# MODUL_RAIL_IN_V100.net
KiCad netlist of a schematic drawn in EAGLE
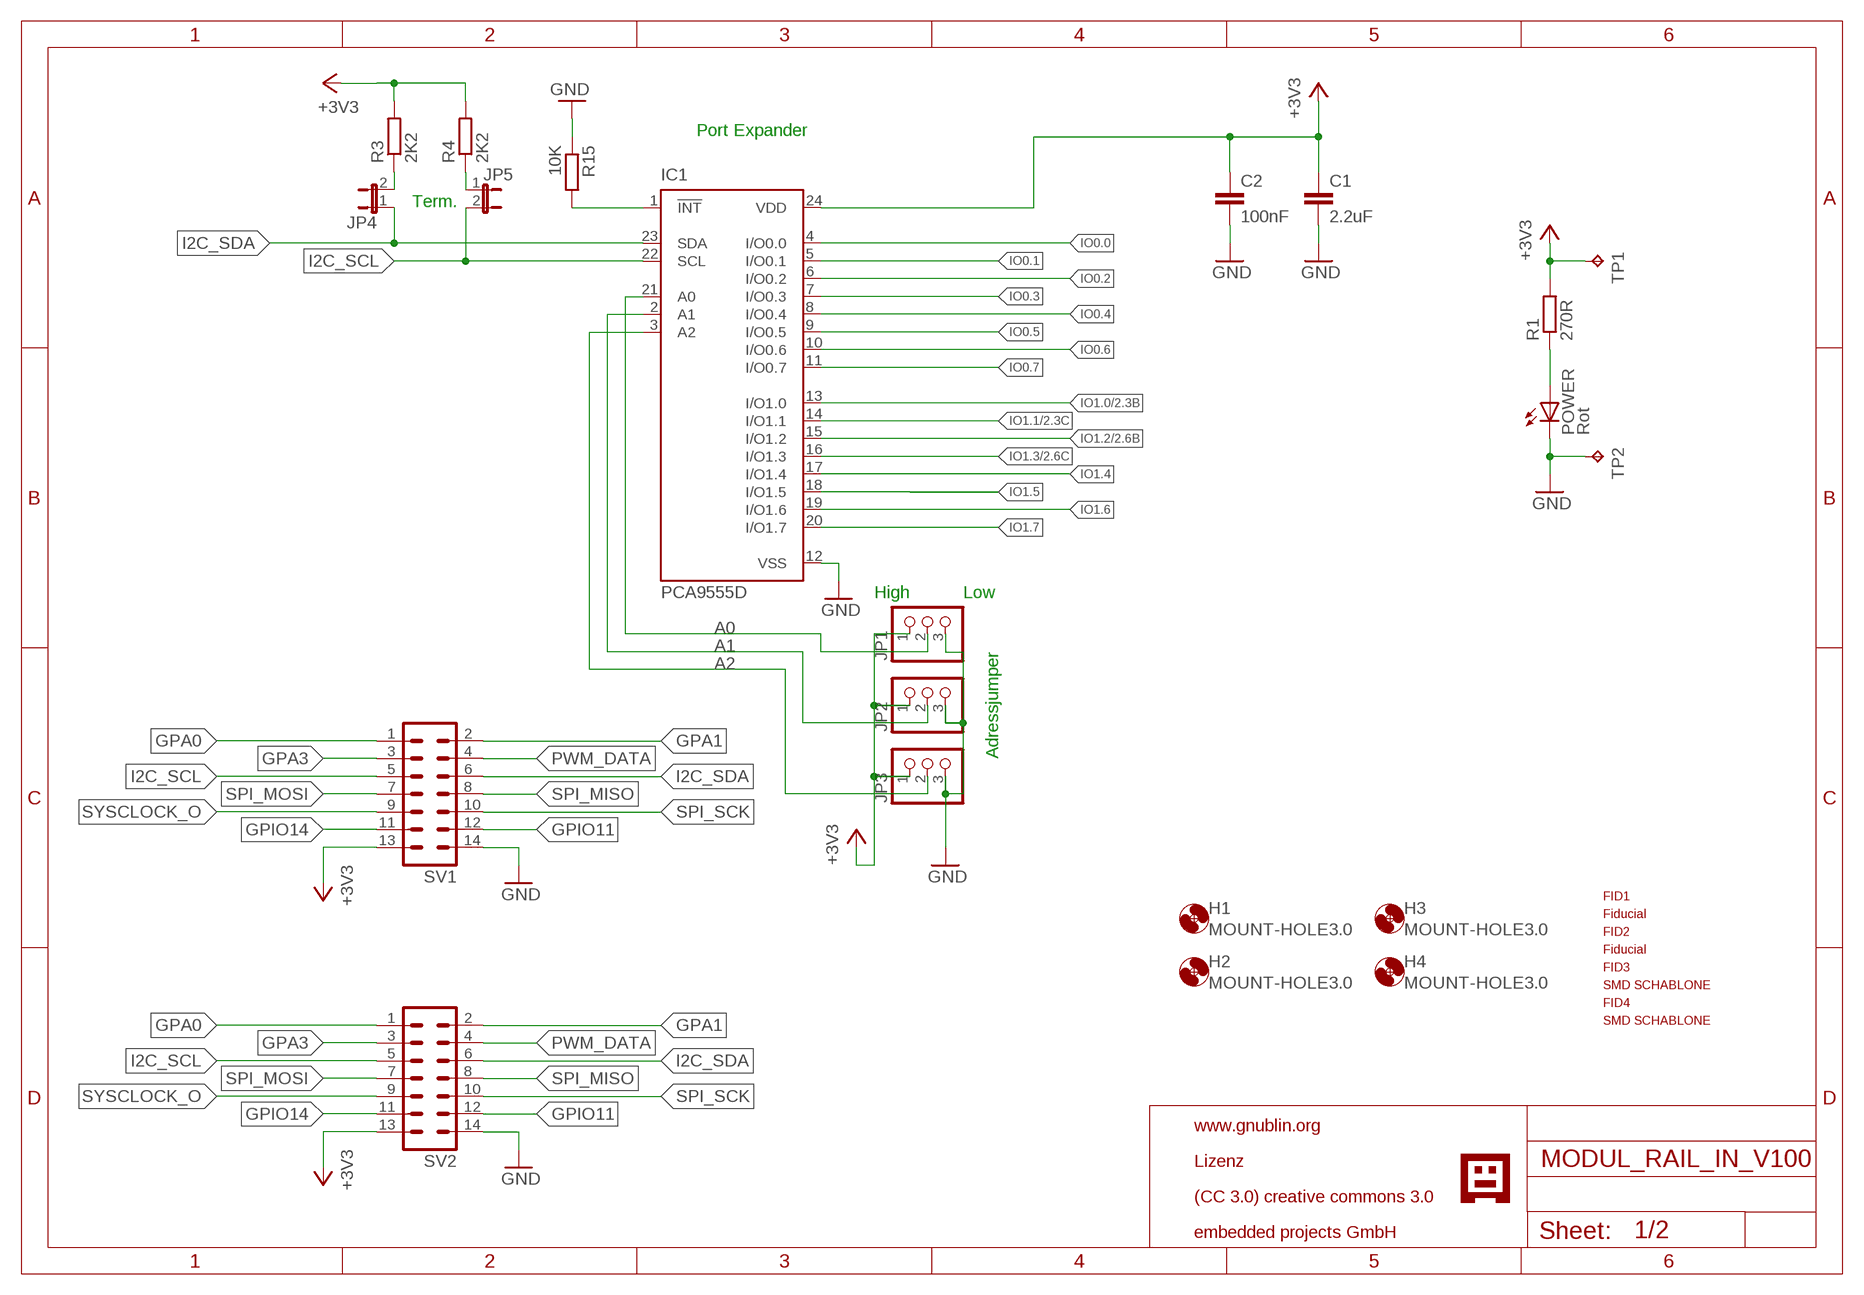
[diagram p0: schematic, sheet 1]
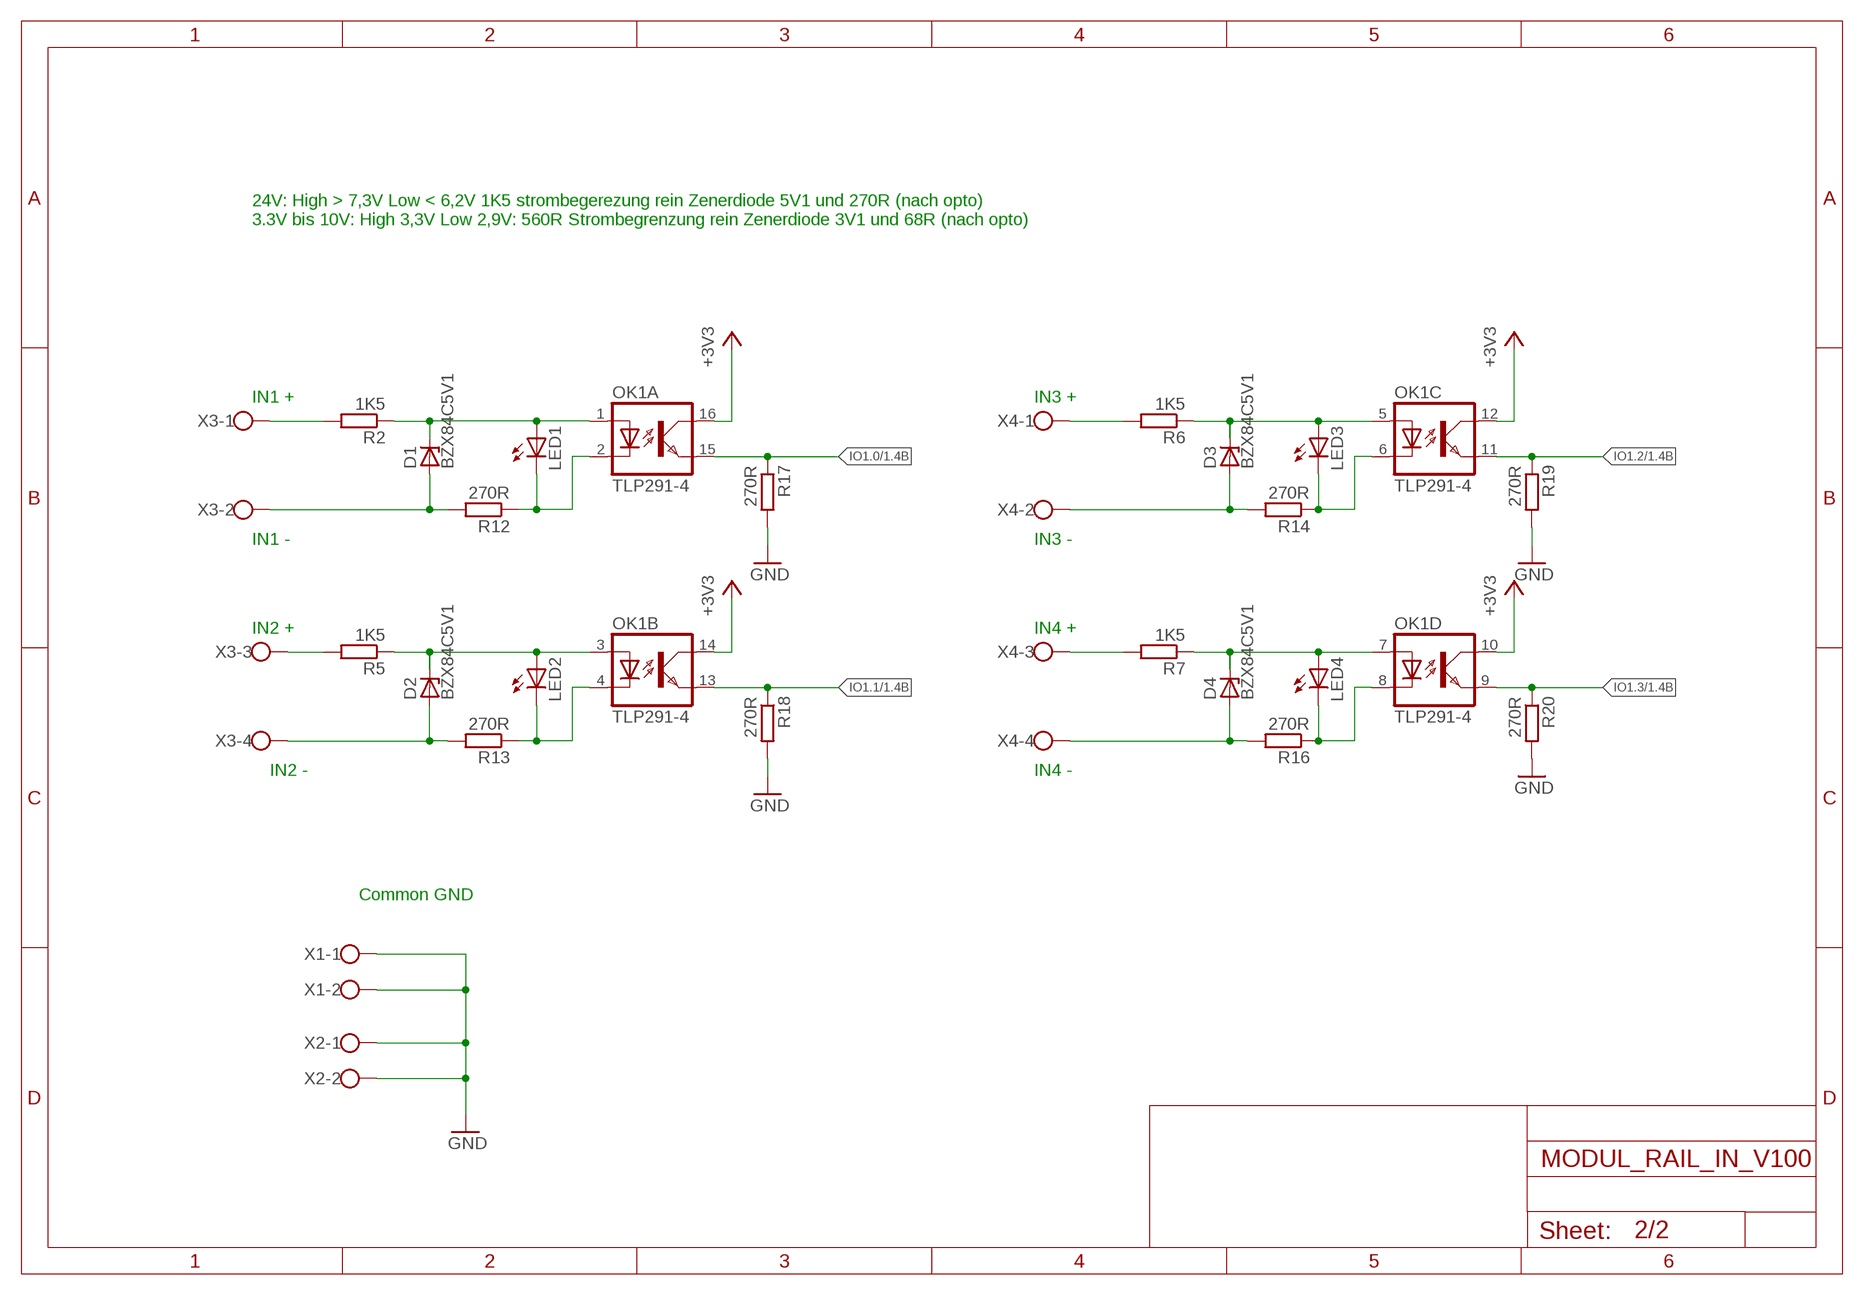
[diagram p1: schematic, sheet 2]

(export (version "E")
  (design (tool "Eeschema 10.0.6"))
  (components
    (comp (ref "C1")
      (value "2.2uF")
      (footprint "eagle-import:C0805")
      (libsource (lib "eagle-import") (part "C-EUC0805"))
    )
    (comp (ref "C2")
      (value "100nF")
      (footprint "eagle-import:C0805")
      (libsource (lib "eagle-import") (part "C-EUC0805"))
    )
    (comp (ref "FID1")
      (value "PASSERMARKEN_FIDUCIAL")
      (footprint "eagle-import:PASSERMARKEN_FIDUCIAL")
      (libsource (lib "eagle-import") (part "PASSERMARKEN_FIDUCIAL"))
    )
    (comp (ref "FID2")
      (value "PASSERMARKEN_FIDUCIAL")
      (footprint "eagle-import:PASSERMARKEN_FIDUCIAL")
      (libsource (lib "eagle-import") (part "PASSERMARKEN_FIDUCIAL"))
    )
    (comp (ref "FID3")
      (value "PASSERMARKEN_FIDUCIAL")
      (footprint "eagle-import:PASSERMARKEN_FIDUCIAL")
      (libsource (lib "eagle-import") (part "SMDSCHABLONE_PASSERMARKEN_FIDUCIAL"))
    )
    (comp (ref "FID4")
      (value "PASSERMARKEN_FIDUCIAL")
      (footprint "eagle-import:PASSERMARKEN_FIDUCIAL")
      (libsource (lib "eagle-import") (part "SMDSCHABLONE_PASSERMARKEN_FIDUCIAL"))
    )
    (comp (ref "H1")
      (value "MOUNT-HOLE3.0")
      (footprint "eagle-import:3,0")
      (libsource (lib "eagle-import") (part "MOUNT-HOLE3.0"))
    )
    (comp (ref "H2")
      (value "MOUNT-HOLE3.0")
      (footprint "eagle-import:3,0")
      (libsource (lib "eagle-import") (part "MOUNT-HOLE3.0"))
    )
    (comp (ref "H3")
      (value "MOUNT-HOLE3.0")
      (footprint "eagle-import:3,0")
      (libsource (lib "eagle-import") (part "MOUNT-HOLE3.0"))
    )
    (comp (ref "H4")
      (value "MOUNT-HOLE3.0")
      (footprint "eagle-import:3,0")
      (libsource (lib "eagle-import") (part "MOUNT-HOLE3.0"))
    )
    (comp (ref "IC1")
      (value "PCA9555D")
      (footprint "eagle-import:SO24")
      (fields (field (name "MPN") "PCA9555DW") (field (name "OC_FARNELL") "8906076"))
      (libsource (lib "eagle-import") (part "PCA9555D"))
    )
    (comp (ref "JP1")
      (value "PINHD-1X3")
      (footprint "eagle-import:1X03")
      (libsource (lib "eagle-import") (part "PINHD-1X3"))
    )
    (comp (ref "JP2")
      (value "PINHD-1X3")
      (footprint "eagle-import:1X03")
      (libsource (lib "eagle-import") (part "PINHD-1X3"))
    )
    (comp (ref "JP3")
      (value "PINHD-1X3")
      (footprint "eagle-import:1X03")
      (libsource (lib "eagle-import") (part "PINHD-1X3"))
    )
    (comp (ref "JP4")
      (value "JP1E")
      (footprint "eagle-import:JP1")
      (libsource (lib "eagle-import") (part "JP1E"))
    )
    (comp (ref "JP5")
      (value "JP1E")
      (footprint "eagle-import:JP1")
      (libsource (lib "eagle-import") (part "JP1E"))
    )
    (comp (ref "POWER")
      (value "Rot")
      (footprint "eagle-import:CHIP-LED0805")
      (libsource (lib "eagle-import") (part "LEDCHIP-LED0805"))
    )
    (comp (ref "R1")
      (value "270R")
      (footprint "eagle-import:R0805")
      (libsource (lib "eagle-import") (part "R-EU_R0805"))
    )
    (comp (ref "R3")
      (value "2K2")
      (footprint "eagle-import:R0805")
      (libsource (lib "eagle-import") (part "R-EU_R0805"))
    )
    (comp (ref "R4")
      (value "2K2")
      (footprint "eagle-import:R0805")
      (libsource (lib "eagle-import") (part "R-EU_R0805"))
    )
    (comp (ref "R15")
      (value "10K")
      (footprint "eagle-import:R0805")
      (libsource (lib "eagle-import") (part "R-EU_R0805"))
    )
    (comp (ref "SV1")
      (value "ML14")
      (footprint "eagle-import:ML14")
      (libsource (lib "eagle-import") (part "ML14"))
    )
    (comp (ref "SV2")
      (value "ML14")
      (footprint "eagle-import:ML14")
      (libsource (lib "eagle-import") (part "ML14"))
    )
    (comp (ref "TP1")
      (value "TPB1,27")
      (footprint "eagle-import:B1,27")
      (libsource (lib "eagle-import") (part "TPB1,27"))
    )
    (comp (ref "TP2")
      (value "TPB1,27")
      (footprint "eagle-import:B1,27")
      (libsource (lib "eagle-import") (part "TPB1,27"))
    )
    (comp (ref "U$2")
      (value "GNUBLINLOGOSIEB")
      (footprint "eagle-import:GNUSIEBDRUCK")
      (libsource (lib "eagle-import") (part "GNUBLINLOGOSIEB"))
    )
    (comp (ref "D1")
      (value "BZX84C5V1")
      (footprint "eagle-import:TO236")
      (libsource (lib "eagle-import") (part "BZX84CSMD"))
    )
    (comp (ref "D2")
      (value "BZX84C5V1")
      (footprint "eagle-import:TO236")
      (libsource (lib "eagle-import") (part "BZX84CSMD"))
    )
    (comp (ref "D3")
      (value "BZX84C5V1")
      (footprint "eagle-import:TO236")
      (libsource (lib "eagle-import") (part "BZX84CSMD"))
    )
    (comp (ref "D4")
      (value "BZX84C5V1")
      (footprint "eagle-import:TO236")
      (libsource (lib "eagle-import") (part "BZX84CSMD"))
    )
    (comp (ref "LED1")
      (value "LEDCHIPLED_0805")
      (footprint "eagle-import:CHIPLED_0805")
      (libsource (lib "eagle-import") (part "LEDCHIPLED_0805"))
    )
    (comp (ref "LED2")
      (value "LEDCHIPLED_0805")
      (footprint "eagle-import:CHIPLED_0805")
      (libsource (lib "eagle-import") (part "LEDCHIPLED_0805"))
    )
    (comp (ref "LED3")
      (value "LEDCHIPLED_0805")
      (footprint "eagle-import:CHIPLED_0805")
      (libsource (lib "eagle-import") (part "LEDCHIPLED_0805"))
    )
    (comp (ref "LED4")
      (value "LEDCHIPLED_0805")
      (footprint "eagle-import:CHIPLED_0805")
      (libsource (lib "eagle-import") (part "LEDCHIPLED_0805"))
    )
    (comp (ref "OK1")
      (value "TLP291-4")
      (footprint "eagle-import:MINI-FLAT-16")
      (libsource (lib "eagle-import") (part "TLP283-4"))
    )
    (comp (ref "R2")
      (value "1K5")
      (footprint "eagle-import:R0805")
      (libsource (lib "eagle-import") (part "R-EU_R0805"))
    )
    (comp (ref "R5")
      (value "1K5")
      (footprint "eagle-import:R0805")
      (libsource (lib "eagle-import") (part "R-EU_R0805"))
    )
    (comp (ref "R6")
      (value "1K5")
      (footprint "eagle-import:R0805")
      (libsource (lib "eagle-import") (part "R-EU_R0805"))
    )
    (comp (ref "R7")
      (value "1K5")
      (footprint "eagle-import:R0805")
      (libsource (lib "eagle-import") (part "R-EU_R0805"))
    )
    (comp (ref "R12")
      (value "270R")
      (footprint "eagle-import:R0805")
      (libsource (lib "eagle-import") (part "R-EU_R0805"))
    )
    (comp (ref "R13")
      (value "270R")
      (footprint "eagle-import:R0805")
      (libsource (lib "eagle-import") (part "R-EU_R0805"))
    )
    (comp (ref "R14")
      (value "270R")
      (footprint "eagle-import:R0805")
      (libsource (lib "eagle-import") (part "R-EU_R0805"))
    )
    (comp (ref "R16")
      (value "270R")
      (footprint "eagle-import:R0805")
      (libsource (lib "eagle-import") (part "R-EU_R0805"))
    )
    (comp (ref "R17")
      (value "270R")
      (footprint "eagle-import:R0805")
      (libsource (lib "eagle-import") (part "R-EU_R0805"))
    )
    (comp (ref "R18")
      (value "270R")
      (footprint "eagle-import:R0805")
      (libsource (lib "eagle-import") (part "R-EU_R0805"))
    )
    (comp (ref "R19")
      (value "270R")
      (footprint "eagle-import:R0805")
      (libsource (lib "eagle-import") (part "R-EU_R0805"))
    )
    (comp (ref "R20")
      (value "270R")
      (footprint "eagle-import:R0805")
      (libsource (lib "eagle-import") (part "R-EU_R0805"))
    )
    (comp (ref "X1")
      (value "W237-02P")
      (footprint "eagle-import:W237-132")
      (libsource (lib "eagle-import") (part "W237-02P"))
    )
    (comp (ref "X2")
      (value "W237-02P")
      (footprint "eagle-import:W237-132")
      (libsource (lib "eagle-import") (part "W237-02P"))
    )
    (comp (ref "X3")
      (value "W237-04P")
      (footprint "eagle-import:W237-4P")
      (libsource (lib "eagle-import") (part "W237-04P"))
    )
    (comp (ref "X4")
      (value "W237-04P")
      (footprint "eagle-import:W237-4P")
      (libsource (lib "eagle-import") (part "W237-04P"))
    )
  )
  (nets
    (net (code "1") (name "+3V3") (class "Default")
      (node (ref "C1") (pin "1") (pinfunction "1_1") (pintype "passive"))
      (node (ref "C2") (pin "1") (pinfunction "1_1") (pintype "passive"))
      (node (ref "IC1") (pin "24") (pinfunction "VDD_24") (pintype "power_in"))
      (node (ref "JP1") (pin "1") (pinfunction "1_1") (pintype "passive"))
      (node (ref "JP2") (pin "1") (pinfunction "1_1") (pintype "passive"))
      (node (ref "JP3") (pin "1") (pinfunction "1_1") (pintype "passive"))
      (node (ref "OK1") (pin "10") (pinfunction "COL_10") (pintype "passive"))
      (node (ref "OK1") (pin "12") (pinfunction "COL_12") (pintype "passive"))
      (node (ref "OK1") (pin "14") (pinfunction "COL_14") (pintype "passive"))
      (node (ref "OK1") (pin "16") (pinfunction "COL_16") (pintype "passive"))
      (node (ref "R1") (pin "2") (pinfunction "2_2") (pintype "passive"))
      (node (ref "R3") (pin "2") (pinfunction "2_2") (pintype "passive"))
      (node (ref "R4") (pin "2") (pinfunction "2_2") (pintype "passive"))
      (node (ref "SV1") (pin "13") (pinfunction "13_13") (pintype "passive"))
      (node (ref "SV2") (pin "13") (pinfunction "13_13") (pintype "passive"))
      (node (ref "TP1") (pin "TP") (pinfunction "TP_TP") (pintype "input"))
    )
    (net (code "2") (name "A0") (class "Default")
      (node (ref "IC1") (pin "21") (pinfunction "A0_21") (pintype "input"))
      (node (ref "JP1") (pin "2") (pinfunction "2_2") (pintype "passive"))
    )
    (net (code "3") (name "A1") (class "Default")
      (node (ref "IC1") (pin "2") (pinfunction "A1_2") (pintype "input"))
      (node (ref "JP2") (pin "2") (pinfunction "2_2") (pintype "passive"))
    )
    (net (code "4") (name "A2") (class "Default")
      (node (ref "IC1") (pin "3") (pinfunction "A2_3") (pintype "input"))
      (node (ref "JP3") (pin "2") (pinfunction "2_2") (pintype "passive"))
    )
    (net (code "5") (name "GND") (class "Default")
      (node (ref "C1") (pin "2") (pinfunction "2_2") (pintype "passive"))
      (node (ref "C2") (pin "2") (pinfunction "2_2") (pintype "passive"))
      (node (ref "IC1") (pin "12") (pinfunction "VSS_12") (pintype "power_in"))
      (node (ref "JP1") (pin "3") (pinfunction "3_3") (pintype "passive"))
      (node (ref "JP2") (pin "3") (pinfunction "3_3") (pintype "passive"))
      (node (ref "JP3") (pin "3") (pinfunction "3_3") (pintype "passive"))
      (node (ref "POWER") (pin "C") (pinfunction "C_C") (pintype "passive"))
      (node (ref "R15") (pin "1") (pinfunction "1_1") (pintype "passive"))
      (node (ref "R17") (pin "2") (pinfunction "2_2") (pintype "passive"))
      (node (ref "R18") (pin "2") (pinfunction "2_2") (pintype "passive"))
      (node (ref "R19") (pin "2") (pinfunction "2_2") (pintype "passive"))
      (node (ref "R20") (pin "2") (pinfunction "2_2") (pintype "passive"))
      (node (ref "SV1") (pin "14") (pinfunction "14_14") (pintype "passive"))
      (node (ref "SV2") (pin "14") (pinfunction "14_14") (pintype "passive"))
      (node (ref "TP2") (pin "TP") (pinfunction "TP_TP") (pintype "input"))
      (node (ref "X1") (pin "1") (pinfunction "KL_1") (pintype "passive"))
      (node (ref "X1") (pin "2") (pinfunction "KL_2") (pintype "passive"))
      (node (ref "X2") (pin "1") (pinfunction "KL_1") (pintype "passive"))
      (node (ref "X2") (pin "2") (pinfunction "KL_2") (pintype "passive"))
    )
    (net (code "6") (name "GPA0") (class "Default")
      (node (ref "SV1") (pin "1") (pinfunction "1_1") (pintype "passive"))
      (node (ref "SV2") (pin "1") (pinfunction "1_1") (pintype "passive"))
    )
    (net (code "7") (name "GPA1") (class "Default")
      (node (ref "SV1") (pin "2") (pinfunction "2_2") (pintype "passive"))
      (node (ref "SV2") (pin "2") (pinfunction "2_2") (pintype "passive"))
    )
    (net (code "8") (name "GPA3") (class "Default")
      (node (ref "SV1") (pin "3") (pinfunction "3_3") (pintype "passive"))
      (node (ref "SV2") (pin "3") (pinfunction "3_3") (pintype "passive"))
    )
    (net (code "9") (name "GPIO11") (class "Default")
      (node (ref "SV1") (pin "12") (pinfunction "12_12") (pintype "passive"))
      (node (ref "SV2") (pin "12") (pinfunction "12_12") (pintype "passive"))
    )
    (net (code "10") (name "GPIO14") (class "Default")
      (node (ref "SV1") (pin "11") (pinfunction "11_11") (pintype "passive"))
      (node (ref "SV2") (pin "11") (pinfunction "11_11") (pintype "passive"))
    )
    (net (code "11") (name "I2C_SCL") (class "Default")
      (node (ref "IC1") (pin "22") (pinfunction "SCL_22") (pintype "input"))
      (node (ref "JP5") (pin "2") (pinfunction "2_2") (pintype "passive"))
      (node (ref "SV1") (pin "5") (pinfunction "5_5") (pintype "passive"))
      (node (ref "SV2") (pin "5") (pinfunction "5_5") (pintype "passive"))
    )
    (net (code "12") (name "I2C_SDA") (class "Default")
      (node (ref "IC1") (pin "23") (pinfunction "SDA_23") (pintype "bidirectional"))
      (node (ref "JP4") (pin "1") (pinfunction "1_1") (pintype "passive"))
      (node (ref "SV1") (pin "6") (pinfunction "6_6") (pintype "passive"))
      (node (ref "SV2") (pin "6") (pinfunction "6_6") (pintype "passive"))
    )
    (net (code "13") (name "IO0.0") (class "Default")
      (node (ref "IC1") (pin "4") (pinfunction "I/O0.0_4") (pintype "bidirectional"))
    )
    (net (code "14") (name "IO0.1") (class "Default")
      (node (ref "IC1") (pin "5") (pinfunction "I/O0.1_5") (pintype "bidirectional"))
    )
    (net (code "15") (name "IO0.2") (class "Default")
      (node (ref "IC1") (pin "6") (pinfunction "I/O0.2_6") (pintype "bidirectional"))
    )
    (net (code "16") (name "IO0.3") (class "Default")
      (node (ref "IC1") (pin "7") (pinfunction "I/O0.3_7") (pintype "bidirectional"))
    )
    (net (code "17") (name "IO0.4") (class "Default")
      (node (ref "IC1") (pin "8") (pinfunction "I/O0.4_8") (pintype "bidirectional"))
    )
    (net (code "18") (name "IO0.5") (class "Default")
      (node (ref "IC1") (pin "9") (pinfunction "I/O0.5_9") (pintype "bidirectional"))
    )
    (net (code "19") (name "IO0.6") (class "Default")
      (node (ref "IC1") (pin "10") (pinfunction "I/O0.6_10") (pintype "bidirectional"))
    )
    (net (code "20") (name "IO0.7") (class "Default")
      (node (ref "IC1") (pin "11") (pinfunction "I/O0.7_11") (pintype "bidirectional"))
    )
    (net (code "21") (name "IO1.0") (class "Default")
      (node (ref "IC1") (pin "13") (pinfunction "I/O1.0_13") (pintype "bidirectional"))
      (node (ref "OK1") (pin "15") (pinfunction "EMIT_15") (pintype "passive"))
      (node (ref "R17") (pin "1") (pinfunction "1_1") (pintype "passive"))
    )
    (net (code "22") (name "IO1.1") (class "Default")
      (node (ref "IC1") (pin "14") (pinfunction "I/O1.1_14") (pintype "bidirectional"))
      (node (ref "OK1") (pin "13") (pinfunction "EMIT_13") (pintype "passive"))
      (node (ref "R18") (pin "1") (pinfunction "1_1") (pintype "passive"))
    )
    (net (code "23") (name "IO1.2") (class "Default")
      (node (ref "IC1") (pin "15") (pinfunction "I/O1.2_15") (pintype "bidirectional"))
      (node (ref "OK1") (pin "11") (pinfunction "EMIT_11") (pintype "passive"))
      (node (ref "R19") (pin "1") (pinfunction "1_1") (pintype "passive"))
    )
    (net (code "24") (name "IO1.3") (class "Default")
      (node (ref "IC1") (pin "16") (pinfunction "I/O1.3_16") (pintype "bidirectional"))
      (node (ref "OK1") (pin "9") (pinfunction "EMIT_9") (pintype "passive"))
      (node (ref "R20") (pin "1") (pinfunction "1_1") (pintype "passive"))
    )
    (net (code "25") (name "IO1.4") (class "Default")
      (node (ref "IC1") (pin "17") (pinfunction "I/O1.4_17") (pintype "bidirectional"))
    )
    (net (code "26") (name "IO1.5") (class "Default")
      (node (ref "IC1") (pin "18") (pinfunction "I/O1.5_18") (pintype "bidirectional"))
    )
    (net (code "27") (name "IO1.6") (class "Default")
      (node (ref "IC1") (pin "19") (pinfunction "I/O1.6_19") (pintype "bidirectional"))
    )
    (net (code "28") (name "IO1.7") (class "Default")
      (node (ref "IC1") (pin "20") (pinfunction "I/O1.7_20") (pintype "bidirectional"))
    )
    (net (code "29") (name "Net-(IC1-~{INT})") (class "Default")
      (node (ref "IC1") (pin "1") (pinfunction "~{INT}_1") (pintype "output"))
      (node (ref "R15") (pin "2") (pinfunction "2_2") (pintype "passive"))
    )
    (net (code "30") (name "Net-(JP4-Pad2)") (class "Default")
      (node (ref "JP4") (pin "2") (pinfunction "2_2") (pintype "passive"))
      (node (ref "R3") (pin "1") (pinfunction "1_1") (pintype "passive"))
    )
    (net (code "31") (name "Net-(JP5-Pad1)") (class "Default")
      (node (ref "JP5") (pin "1") (pinfunction "1_1") (pintype "passive"))
      (node (ref "R4") (pin "1") (pinfunction "1_1") (pintype "passive"))
    )
    (net (code "32") (name "Net-(OK1A-A)") (class "Default")
      (node (ref "D1") (pin "C") (pinfunction "C_C") (pintype "passive"))
      (node (ref "LED1") (pin "A") (pinfunction "A_A") (pintype "passive"))
      (node (ref "OK1") (pin "1") (pinfunction "A_1") (pintype "passive"))
      (node (ref "R2") (pin "1") (pinfunction "1_1") (pintype "passive"))
    )
    (net (code "33") (name "Net-(OK1A-C)") (class "Default")
      (node (ref "LED1") (pin "C") (pinfunction "C_C") (pintype "passive"))
      (node (ref "OK1") (pin "2") (pinfunction "C_2") (pintype "passive"))
      (node (ref "R12") (pin "1") (pinfunction "1_1") (pintype "passive"))
    )
    (net (code "34") (name "Net-(OK1B-A)") (class "Default")
      (node (ref "D2") (pin "C") (pinfunction "C_C") (pintype "passive"))
      (node (ref "LED2") (pin "A") (pinfunction "A_A") (pintype "passive"))
      (node (ref "OK1") (pin "3") (pinfunction "A_3") (pintype "passive"))
      (node (ref "R5") (pin "1") (pinfunction "1_1") (pintype "passive"))
    )
    (net (code "35") (name "Net-(OK1B-C)") (class "Default")
      (node (ref "LED2") (pin "C") (pinfunction "C_C") (pintype "passive"))
      (node (ref "OK1") (pin "4") (pinfunction "C_4") (pintype "passive"))
      (node (ref "R13") (pin "1") (pinfunction "1_1") (pintype "passive"))
    )
    (net (code "36") (name "Net-(OK1C-A)") (class "Default")
      (node (ref "D3") (pin "C") (pinfunction "C_C") (pintype "passive"))
      (node (ref "LED3") (pin "A") (pinfunction "A_A") (pintype "passive"))
      (node (ref "OK1") (pin "5") (pinfunction "A_5") (pintype "passive"))
      (node (ref "R6") (pin "1") (pinfunction "1_1") (pintype "passive"))
    )
    (net (code "37") (name "Net-(OK1C-C)") (class "Default")
      (node (ref "LED3") (pin "C") (pinfunction "C_C") (pintype "passive"))
      (node (ref "OK1") (pin "6") (pinfunction "C_6") (pintype "passive"))
      (node (ref "R14") (pin "1") (pinfunction "1_1") (pintype "passive"))
    )
    (net (code "38") (name "Net-(OK1D-A)") (class "Default")
      (node (ref "D4") (pin "C") (pinfunction "C_C") (pintype "passive"))
      (node (ref "LED4") (pin "A") (pinfunction "A_A") (pintype "passive"))
      (node (ref "OK1") (pin "7") (pinfunction "A_7") (pintype "passive"))
      (node (ref "R7") (pin "1") (pinfunction "1_1") (pintype "passive"))
    )
    (net (code "39") (name "Net-(OK1D-C)") (class "Default")
      (node (ref "LED4") (pin "C") (pinfunction "C_C") (pintype "passive"))
      (node (ref "OK1") (pin "8") (pinfunction "C_8") (pintype "passive"))
      (node (ref "R16") (pin "1") (pinfunction "1_1") (pintype "passive"))
    )
    (net (code "40") (name "Net-(POWER-PadA)") (class "Default")
      (node (ref "POWER") (pin "A") (pinfunction "A_A") (pintype "passive"))
      (node (ref "R1") (pin "1") (pinfunction "1_1") (pintype "passive"))
    )
    (net (code "41") (name "Net-(X3A-KL)") (class "Default")
      (node (ref "R2") (pin "2") (pinfunction "2_2") (pintype "passive"))
      (node (ref "X3") (pin "1") (pinfunction "KL_1") (pintype "passive"))
    )
    (net (code "42") (name "Net-(X3B-KL)") (class "Default")
      (node (ref "D1") (pin "A") (pinfunction "A_A") (pintype "passive"))
      (node (ref "R12") (pin "2") (pinfunction "2_2") (pintype "passive"))
      (node (ref "X3") (pin "2") (pinfunction "KL_2") (pintype "passive"))
    )
    (net (code "43") (name "Net-(X3C-KL)") (class "Default")
      (node (ref "R5") (pin "2") (pinfunction "2_2") (pintype "passive"))
      (node (ref "X3") (pin "3") (pinfunction "KL_3") (pintype "passive"))
    )
    (net (code "44") (name "Net-(X3D-KL)") (class "Default")
      (node (ref "D2") (pin "A") (pinfunction "A_A") (pintype "passive"))
      (node (ref "R13") (pin "2") (pinfunction "2_2") (pintype "passive"))
      (node (ref "X3") (pin "4") (pinfunction "KL_4") (pintype "passive"))
    )
    (net (code "45") (name "Net-(X4A-KL)") (class "Default")
      (node (ref "R6") (pin "2") (pinfunction "2_2") (pintype "passive"))
      (node (ref "X4") (pin "1") (pinfunction "KL_1") (pintype "passive"))
    )
    (net (code "46") (name "Net-(X4B-KL)") (class "Default")
      (node (ref "D3") (pin "A") (pinfunction "A_A") (pintype "passive"))
      (node (ref "R14") (pin "2") (pinfunction "2_2") (pintype "passive"))
      (node (ref "X4") (pin "2") (pinfunction "KL_2") (pintype "passive"))
    )
    (net (code "47") (name "Net-(X4C-KL)") (class "Default")
      (node (ref "R7") (pin "2") (pinfunction "2_2") (pintype "passive"))
      (node (ref "X4") (pin "3") (pinfunction "KL_3") (pintype "passive"))
    )
    (net (code "48") (name "Net-(X4D-KL)") (class "Default")
      (node (ref "D4") (pin "A") (pinfunction "A_A") (pintype "passive"))
      (node (ref "R16") (pin "2") (pinfunction "2_2") (pintype "passive"))
      (node (ref "X4") (pin "4") (pinfunction "KL_4") (pintype "passive"))
    )
    (net (code "49") (name "PWM_DATA") (class "Default")
      (node (ref "SV1") (pin "4") (pinfunction "4_4") (pintype "passive"))
      (node (ref "SV2") (pin "4") (pinfunction "4_4") (pintype "passive"))
    )
    (net (code "50") (name "SPI_MISO") (class "Default")
      (node (ref "SV1") (pin "8") (pinfunction "8_8") (pintype "passive"))
      (node (ref "SV2") (pin "8") (pinfunction "8_8") (pintype "passive"))
    )
    (net (code "51") (name "SPI_MOSI") (class "Default")
      (node (ref "SV1") (pin "7") (pinfunction "7_7") (pintype "passive"))
      (node (ref "SV2") (pin "7") (pinfunction "7_7") (pintype "passive"))
    )
    (net (code "52") (name "SPI_SCK") (class "Default")
      (node (ref "SV1") (pin "10") (pinfunction "10_10") (pintype "passive"))
      (node (ref "SV2") (pin "10") (pinfunction "10_10") (pintype "passive"))
    )
    (net (code "53") (name "SYSCLOCK_O") (class "Default")
      (node (ref "SV1") (pin "9") (pinfunction "9_9") (pintype "passive"))
      (node (ref "SV2") (pin "9") (pinfunction "9_9") (pintype "passive"))
    )
  )
)
